# Easyhub.net
KiCad netlist of a schematic drawn in EasyEDA Pro
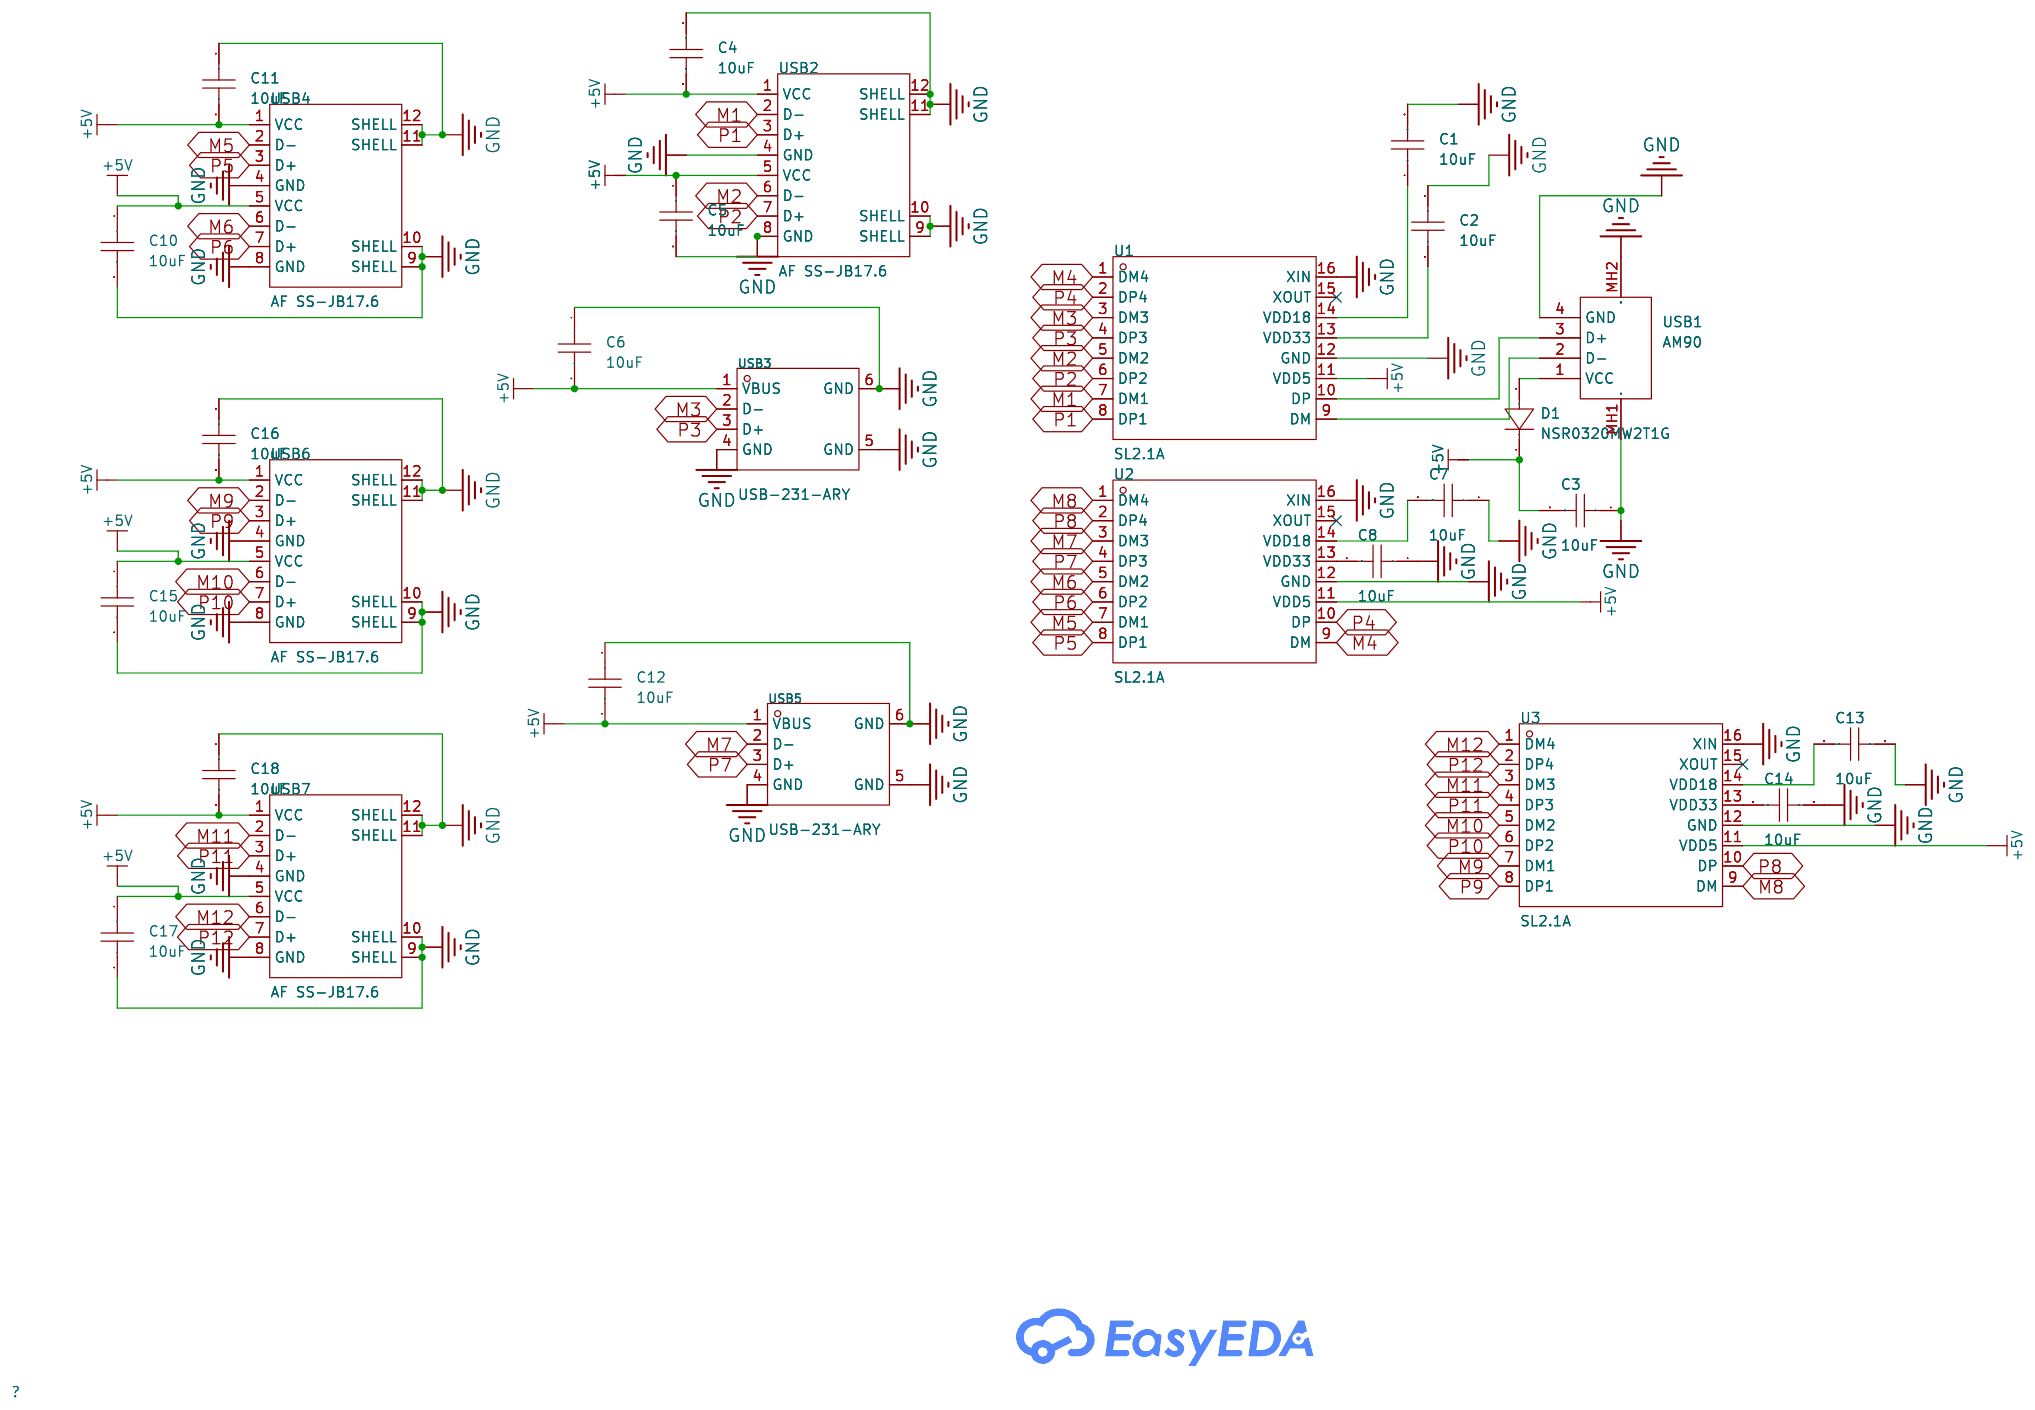
[diagram p0: schematic sheet]

(export (version "E")
  (design (tool "Eeschema 10.0.6"))
  (components
    (comp (ref "C1")
      (value "10uF")
      (footprint "easyedapro:C0603")
      (description "Capacitance:10uF Tolerance:±10% Tolerance:±10% Voltage Rating:10V Temperature Coefficient:X5R")
      (fields
        (field (name "Manufacturer Part") "CL10A106KP8NNNC")
        (field (name "Manufacturer") "SAMSUNG(三星)")
      )
      (libsource (lib "easyedapro") (part "CAP"))
    )
    (comp (ref "C2")
      (value "10uF")
      (footprint "easyedapro:C0603")
      (description "Capacitance:10uF Tolerance:±10% Tolerance:±10% Voltage Rating:10V Temperature Coefficient:X5R")
      (fields
        (field (name "Manufacturer Part") "CL10A106KP8NNNC")
        (field (name "Manufacturer") "SAMSUNG(三星)")
      )
      (libsource (lib "easyedapro") (part "CAP"))
    )
    (comp (ref "C3")
      (value "10uF")
      (footprint "easyedapro:C0603")
      (description "Capacitance:10uF Tolerance:±10% Tolerance:±10% Voltage Rating:10V Temperature Coefficient:X5R")
      (fields
        (field (name "Manufacturer Part") "CL10A106KP8NNNC")
        (field (name "Manufacturer") "SAMSUNG(三星)")
      )
      (libsource (lib "easyedapro") (part "CAP"))
    )
    (comp (ref "C4")
      (value "10uF")
      (footprint "easyedapro:C0603")
      (description "Capacitance:10uF Tolerance:±10% Tolerance:±10% Voltage Rating:10V Temperature Coefficient:X5R")
      (fields
        (field (name "Manufacturer Part") "CL10A106KP8NNNC")
        (field (name "Manufacturer") "SAMSUNG(三星)")
      )
      (libsource (lib "easyedapro") (part "CAP"))
    )
    (comp (ref "C5")
      (value "10uF")
      (footprint "easyedapro:C0603")
      (description "Capacitance:10uF Tolerance:±10% Tolerance:±10% Voltage Rating:10V Temperature Coefficient:X5R")
      (fields
        (field (name "Manufacturer Part") "CL10A106KP8NNNC")
        (field (name "Manufacturer") "SAMSUNG(三星)")
      )
      (libsource (lib "easyedapro") (part "CAP"))
    )
    (comp (ref "C6")
      (value "10uF")
      (footprint "easyedapro:C0603")
      (description "Capacitance:10uF Tolerance:±10% Tolerance:±10% Voltage Rating:10V Temperature Coefficient:X5R")
      (fields
        (field (name "Manufacturer Part") "CL10A106KP8NNNC")
        (field (name "Manufacturer") "SAMSUNG(三星)")
      )
      (libsource (lib "easyedapro") (part "CAP"))
    )
    (comp (ref "C7")
      (value "10uF")
      (footprint "easyedapro:C0603")
      (description "Capacitance:10uF Tolerance:±10% Tolerance:±10% Voltage Rating:10V Temperature Coefficient:X5R")
      (fields
        (field (name "Manufacturer Part") "CL10A106KP8NNNC")
        (field (name "Manufacturer") "SAMSUNG(三星)")
      )
      (libsource (lib "easyedapro") (part "CAP"))
    )
    (comp (ref "C8")
      (value "10uF")
      (footprint "easyedapro:C0603")
      (description "Capacitance:10uF Tolerance:±10% Tolerance:±10% Voltage Rating:10V Temperature Coefficient:X5R")
      (fields
        (field (name "Manufacturer Part") "CL10A106KP8NNNC")
        (field (name "Manufacturer") "SAMSUNG(三星)")
      )
      (libsource (lib "easyedapro") (part "CAP"))
    )
    (comp (ref "C10")
      (value "10uF")
      (footprint "easyedapro:C0603")
      (description "Capacitance:10uF Tolerance:±10% Tolerance:±10% Voltage Rating:10V Temperature Coefficient:X5R")
      (fields
        (field (name "Manufacturer Part") "CL10A106KP8NNNC")
        (field (name "Manufacturer") "SAMSUNG(三星)")
      )
      (libsource (lib "easyedapro") (part "CAP"))
    )
    (comp (ref "C11")
      (value "10uF")
      (footprint "easyedapro:C0603")
      (description "Capacitance:10uF Tolerance:±10% Tolerance:±10% Voltage Rating:10V Temperature Coefficient:X5R")
      (fields
        (field (name "Manufacturer Part") "CL10A106KP8NNNC")
        (field (name "Manufacturer") "SAMSUNG(三星)")
      )
      (libsource (lib "easyedapro") (part "CAP"))
    )
    (comp (ref "C12")
      (value "10uF")
      (footprint "easyedapro:C0603")
      (description "Capacitance:10uF Tolerance:±10% Tolerance:±10% Voltage Rating:10V Temperature Coefficient:X5R")
      (fields
        (field (name "Manufacturer Part") "CL10A106KP8NNNC")
        (field (name "Manufacturer") "SAMSUNG(三星)")
      )
      (libsource (lib "easyedapro") (part "CAP"))
    )
    (comp (ref "C13")
      (value "10uF")
      (footprint "easyedapro:C0603")
      (description "Capacitance:10uF Tolerance:±10% Tolerance:±10% Voltage Rating:10V Temperature Coefficient:X5R")
      (fields
        (field (name "Manufacturer Part") "CL10A106KP8NNNC")
        (field (name "Manufacturer") "SAMSUNG(三星)")
      )
      (libsource (lib "easyedapro") (part "CAP"))
    )
    (comp (ref "C14")
      (value "10uF")
      (footprint "easyedapro:C0603")
      (description "Capacitance:10uF Tolerance:±10% Tolerance:±10% Voltage Rating:10V Temperature Coefficient:X5R")
      (fields
        (field (name "Manufacturer Part") "CL10A106KP8NNNC")
        (field (name "Manufacturer") "SAMSUNG(三星)")
      )
      (libsource (lib "easyedapro") (part "CAP"))
    )
    (comp (ref "C15")
      (value "10uF")
      (footprint "easyedapro:C0603")
      (description "Capacitance:10uF Tolerance:±10% Tolerance:±10% Voltage Rating:10V Temperature Coefficient:X5R")
      (fields
        (field (name "Manufacturer Part") "CL10A106KP8NNNC")
        (field (name "Manufacturer") "SAMSUNG(三星)")
      )
      (libsource (lib "easyedapro") (part "CAP"))
    )
    (comp (ref "C16")
      (value "10uF")
      (footprint "easyedapro:C0603")
      (description "Capacitance:10uF Tolerance:±10% Tolerance:±10% Voltage Rating:10V Temperature Coefficient:X5R")
      (fields
        (field (name "Manufacturer Part") "CL10A106KP8NNNC")
        (field (name "Manufacturer") "SAMSUNG(三星)")
      )
      (libsource (lib "easyedapro") (part "CAP"))
    )
    (comp (ref "C17")
      (value "10uF")
      (footprint "easyedapro:C0603")
      (description "Capacitance:10uF Tolerance:±10% Tolerance:±10% Voltage Rating:10V Temperature Coefficient:X5R")
      (fields
        (field (name "Manufacturer Part") "CL10A106KP8NNNC")
        (field (name "Manufacturer") "SAMSUNG(三星)")
      )
      (libsource (lib "easyedapro") (part "CAP"))
    )
    (comp (ref "C18")
      (value "10uF")
      (footprint "easyedapro:C0603")
      (description "Capacitance:10uF Tolerance:±10% Tolerance:±10% Voltage Rating:10V Temperature Coefficient:X5R")
      (fields
        (field (name "Manufacturer Part") "CL10A106KP8NNNC")
        (field (name "Manufacturer") "SAMSUNG(三星)")
      )
      (libsource (lib "easyedapro") (part "CAP"))
    )
    (comp (ref "D1")
      (value "NSR0320MW2T1G")
      (footprint "easyedapro:SMA_L4.4-W2.8-LS5.4-RD")
      (fields (field (name "Manufacturer") "onsemi(安森美)"))
      (libsource (lib "easyedapro") (part "D_1N4007"))
    )
    (comp (ref "U1")
      (value "SL2.1A")
      (footprint "easyedapro:SOP-16_L10.0-W3.9-P1.27-LS6.0-BL")
      (fields (field (name "Manufacturer") "CoreChips(和芯润德)"))
      (libsource (lib "easyedapro") (part "SL2.1A_C6798314"))
    )
    (comp (ref "U2")
      (value "SL2.1A")
      (footprint "easyedapro:SOP-16_L10.0-W3.9-P1.27-LS6.0-BL")
      (fields (field (name "Manufacturer") "CoreChips(和芯润德)"))
      (libsource (lib "easyedapro") (part "SL2.1A_C6798314"))
    )
    (comp (ref "U3")
      (value "SL2.1A")
      (footprint "easyedapro:SOP-16_L10.0-W3.9-P1.27-LS6.0-BL")
      (fields (field (name "Manufacturer") "CoreChips(和芯润德)"))
      (libsource (lib "easyedapro") (part "SL2.1A_C6798314"))
    )
    (comp (ref "USB1")
      (value "AM90")
      (footprint "easyedapro:USB-AM-TH_AM90")
      (fields (field (name "Manufacturer") "SHOU HAN(首韩)"))
      (libsource (lib "easyedapro") (part "AM90"))
    )
    (comp (ref "USB2")
      (value "AF SS-JB17.6")
      (footprint "easyedapro:USB-A-TH_AF-SS-JB17.6")
      (fields (field (name "Manufacturer") "SHOU HAN(首韩)"))
      (libsource (lib "easyedapro") (part "AF SS-JB17.6"))
    )
    (comp (ref "USB3")
      (value "USB-231-ARY")
      (footprint "easyedapro:USB-A-TH_USB-231-ARY")
      (fields (field (name "Manufacturer") "XUNPU(讯普)"))
      (libsource (lib "easyedapro") (part "USB-231-ARY"))
    )
    (comp (ref "USB4")
      (value "AF SS-JB17.6")
      (footprint "easyedapro:USB-A-TH_AF-SS-JB17.6")
      (fields (field (name "Manufacturer") "SHOU HAN(首韩)"))
      (libsource (lib "easyedapro") (part "AF SS-JB17.6"))
    )
    (comp (ref "USB5")
      (value "USB-231-ARY")
      (footprint "easyedapro:USB-A-TH_USB-231-ARY")
      (fields (field (name "Manufacturer") "XUNPU(讯普)"))
      (libsource (lib "easyedapro") (part "USB-231-ARY"))
    )
    (comp (ref "USB6")
      (value "AF SS-JB17.6")
      (footprint "easyedapro:USB-A-TH_AF-SS-JB17.6")
      (fields (field (name "Manufacturer") "SHOU HAN(首韩)"))
      (libsource (lib "easyedapro") (part "AF SS-JB17.6"))
    )
    (comp (ref "USB7")
      (value "AF SS-JB17.6")
      (footprint "easyedapro:USB-A-TH_AF-SS-JB17.6")
      (fields (field (name "Manufacturer") "SHOU HAN(首韩)"))
      (libsource (lib "easyedapro") (part "AF SS-JB17.6"))
    )
  )
  (nets
    (net (code "1") (name "+5V") (class "Default")
      (node (ref "C10") (pin "1") (pinfunction "1_1") (pintype "input"))
      (node (ref "C11") (pin "2") (pinfunction "2_2") (pintype "input"))
      (node (ref "C12") (pin "2") (pinfunction "2_2") (pintype "input"))
      (node (ref "C15") (pin "1") (pinfunction "1_1") (pintype "input"))
      (node (ref "C16") (pin "2") (pinfunction "2_2") (pintype "input"))
      (node (ref "C17") (pin "1") (pinfunction "1_1") (pintype "input"))
      (node (ref "C18") (pin "2") (pinfunction "2_2") (pintype "input"))
      (node (ref "C3") (pin "2") (pinfunction "2_2") (pintype "input"))
      (node (ref "C4") (pin "2") (pinfunction "2_2") (pintype "input"))
      (node (ref "C5") (pin "1") (pinfunction "1_1") (pintype "input"))
      (node (ref "C6") (pin "2") (pinfunction "2_2") (pintype "input"))
      (node (ref "D1") (pin "1") (pinfunction "K_1") (pintype "input"))
      (node (ref "U1") (pin "11") (pinfunction "VDD5_11") (pintype "unspecified"))
      (node (ref "U2") (pin "11") (pinfunction "VDD5_11") (pintype "unspecified"))
      (node (ref "U3") (pin "11") (pinfunction "VDD5_11") (pintype "unspecified"))
      (node (ref "USB2") (pin "1") (pinfunction "VCC_1") (pintype "unspecified"))
      (node (ref "USB2") (pin "5") (pinfunction "VCC_5") (pintype "unspecified"))
      (node (ref "USB3") (pin "1") (pinfunction "VBUS_1") (pintype "input"))
      (node (ref "USB4") (pin "1") (pinfunction "VCC_1") (pintype "unspecified"))
      (node (ref "USB4") (pin "5") (pinfunction "VCC_5") (pintype "unspecified"))
      (node (ref "USB5") (pin "1") (pinfunction "VBUS_1") (pintype "input"))
      (node (ref "USB6") (pin "1") (pinfunction "VCC_1") (pintype "unspecified"))
      (node (ref "USB6") (pin "5") (pinfunction "VCC_5") (pintype "unspecified"))
      (node (ref "USB7") (pin "1") (pinfunction "VCC_1") (pintype "unspecified"))
      (node (ref "USB7") (pin "5") (pinfunction "VCC_5") (pintype "unspecified"))
    )
    (net (code "2") (name "GND") (class "Default")
      (node (ref "C1") (pin "2") (pinfunction "2_2") (pintype "input"))
      (node (ref "C10") (pin "2") (pinfunction "2_2") (pintype "input"))
      (node (ref "C11") (pin "1") (pinfunction "1_1") (pintype "input"))
      (node (ref "C12") (pin "1") (pinfunction "1_1") (pintype "input"))
      (node (ref "C13") (pin "1") (pinfunction "1_1") (pintype "input"))
      (node (ref "C14") (pin "1") (pinfunction "1_1") (pintype "input"))
      (node (ref "C15") (pin "2") (pinfunction "2_2") (pintype "input"))
      (node (ref "C16") (pin "1") (pinfunction "1_1") (pintype "input"))
      (node (ref "C17") (pin "2") (pinfunction "2_2") (pintype "input"))
      (node (ref "C18") (pin "1") (pinfunction "1_1") (pintype "input"))
      (node (ref "C2") (pin "1") (pinfunction "1_1") (pintype "input"))
      (node (ref "C3") (pin "1") (pinfunction "1_1") (pintype "input"))
      (node (ref "C4") (pin "1") (pinfunction "1_1") (pintype "input"))
      (node (ref "C5") (pin "2") (pinfunction "2_2") (pintype "input"))
      (node (ref "C6") (pin "1") (pinfunction "1_1") (pintype "input"))
      (node (ref "C7") (pin "1") (pinfunction "1_1") (pintype "input"))
      (node (ref "C8") (pin "1") (pinfunction "1_1") (pintype "input"))
      (node (ref "U1") (pin "12") (pinfunction "GND_12") (pintype "unspecified"))
      (node (ref "U1") (pin "16") (pinfunction "XIN_16") (pintype "unspecified"))
      (node (ref "U2") (pin "12") (pinfunction "GND_12") (pintype "unspecified"))
      (node (ref "U2") (pin "16") (pinfunction "XIN_16") (pintype "unspecified"))
      (node (ref "U3") (pin "12") (pinfunction "GND_12") (pintype "unspecified"))
      (node (ref "U3") (pin "16") (pinfunction "XIN_16") (pintype "unspecified"))
      (node (ref "USB1") (pin "4") (pinfunction "GND_4") (pintype "input"))
      (node (ref "USB1") (pin "MH1") (pinfunction "MH1_MH1") (pintype "unspecified"))
      (node (ref "USB1") (pin "MH2") (pinfunction "MH2_MH2") (pintype "unspecified"))
      (node (ref "USB2") (pin "10") (pinfunction "SHELL_10") (pintype "unspecified"))
      (node (ref "USB2") (pin "11") (pinfunction "SHELL_11") (pintype "unspecified"))
      (node (ref "USB2") (pin "12") (pinfunction "SHELL_12") (pintype "unspecified"))
      (node (ref "USB2") (pin "4") (pinfunction "GND_4") (pintype "unspecified"))
      (node (ref "USB2") (pin "8") (pinfunction "GND_8") (pintype "unspecified"))
      (node (ref "USB2") (pin "9") (pinfunction "SHELL_9") (pintype "unspecified"))
      (node (ref "USB3") (pin "4") (pinfunction "GND_4") (pintype "input"))
      (node (ref "USB3") (pin "5") (pinfunction "GND_5") (pintype "input"))
      (node (ref "USB3") (pin "6") (pinfunction "GND_6") (pintype "input"))
      (node (ref "USB4") (pin "10") (pinfunction "SHELL_10") (pintype "unspecified"))
      (node (ref "USB4") (pin "11") (pinfunction "SHELL_11") (pintype "unspecified"))
      (node (ref "USB4") (pin "12") (pinfunction "SHELL_12") (pintype "unspecified"))
      (node (ref "USB4") (pin "4") (pinfunction "GND_4") (pintype "unspecified"))
      (node (ref "USB4") (pin "8") (pinfunction "GND_8") (pintype "unspecified"))
      (node (ref "USB4") (pin "9") (pinfunction "SHELL_9") (pintype "unspecified"))
      (node (ref "USB5") (pin "4") (pinfunction "GND_4") (pintype "input"))
      (node (ref "USB5") (pin "5") (pinfunction "GND_5") (pintype "input"))
      (node (ref "USB5") (pin "6") (pinfunction "GND_6") (pintype "input"))
      (node (ref "USB6") (pin "10") (pinfunction "SHELL_10") (pintype "unspecified"))
      (node (ref "USB6") (pin "11") (pinfunction "SHELL_11") (pintype "unspecified"))
      (node (ref "USB6") (pin "12") (pinfunction "SHELL_12") (pintype "unspecified"))
      (node (ref "USB6") (pin "4") (pinfunction "GND_4") (pintype "unspecified"))
      (node (ref "USB6") (pin "8") (pinfunction "GND_8") (pintype "unspecified"))
      (node (ref "USB6") (pin "9") (pinfunction "SHELL_9") (pintype "unspecified"))
      (node (ref "USB7") (pin "10") (pinfunction "SHELL_10") (pintype "unspecified"))
      (node (ref "USB7") (pin "11") (pinfunction "SHELL_11") (pintype "unspecified"))
      (node (ref "USB7") (pin "12") (pinfunction "SHELL_12") (pintype "unspecified"))
      (node (ref "USB7") (pin "4") (pinfunction "GND_4") (pintype "unspecified"))
      (node (ref "USB7") (pin "8") (pinfunction "GND_8") (pintype "unspecified"))
      (node (ref "USB7") (pin "9") (pinfunction "SHELL_9") (pintype "unspecified"))
    )
    (net (code "3") (name "M1") (class "Default")
      (node (ref "U1") (pin "7") (pinfunction "DM1_7") (pintype "unspecified"))
      (node (ref "USB2") (pin "2") (pinfunction "D-_2") (pintype "unspecified"))
    )
    (net (code "4") (name "M2") (class "Default")
      (node (ref "U1") (pin "5") (pinfunction "DM2_5") (pintype "unspecified"))
      (node (ref "USB2") (pin "6") (pinfunction "D-_6") (pintype "unspecified"))
    )
    (net (code "5") (name "M3") (class "Default")
      (node (ref "U1") (pin "3") (pinfunction "DM3_3") (pintype "unspecified"))
      (node (ref "USB3") (pin "2") (pinfunction "D-_2") (pintype "input"))
    )
    (net (code "6") (name "M4") (class "Default")
      (node (ref "U1") (pin "1") (pinfunction "DM4_1") (pintype "unspecified"))
      (node (ref "U2") (pin "9") (pinfunction "DM_9") (pintype "unspecified"))
    )
    (net (code "7") (name "M5") (class "Default")
      (node (ref "U2") (pin "7") (pinfunction "DM1_7") (pintype "unspecified"))
      (node (ref "USB4") (pin "2") (pinfunction "D-_2") (pintype "unspecified"))
    )
    (net (code "8") (name "M6") (class "Default")
      (node (ref "U2") (pin "5") (pinfunction "DM2_5") (pintype "unspecified"))
      (node (ref "USB4") (pin "6") (pinfunction "D-_6") (pintype "unspecified"))
    )
    (net (code "9") (name "M7") (class "Default")
      (node (ref "U2") (pin "3") (pinfunction "DM3_3") (pintype "unspecified"))
      (node (ref "USB5") (pin "2") (pinfunction "D-_2") (pintype "input"))
    )
    (net (code "10") (name "M8") (class "Default")
      (node (ref "U2") (pin "1") (pinfunction "DM4_1") (pintype "unspecified"))
      (node (ref "U3") (pin "9") (pinfunction "DM_9") (pintype "unspecified"))
    )
    (net (code "11") (name "M9") (class "Default")
      (node (ref "U3") (pin "7") (pinfunction "DM1_7") (pintype "unspecified"))
      (node (ref "USB6") (pin "2") (pinfunction "D-_2") (pintype "unspecified"))
    )
    (net (code "12") (name "M10") (class "Default")
      (node (ref "U3") (pin "5") (pinfunction "DM2_5") (pintype "unspecified"))
      (node (ref "USB6") (pin "6") (pinfunction "D-_6") (pintype "unspecified"))
    )
    (net (code "13") (name "M11") (class "Default")
      (node (ref "U3") (pin "3") (pinfunction "DM3_3") (pintype "unspecified"))
      (node (ref "USB7") (pin "2") (pinfunction "D-_2") (pintype "unspecified"))
    )
    (net (code "14") (name "M12") (class "Default")
      (node (ref "U3") (pin "1") (pinfunction "DM4_1") (pintype "unspecified"))
      (node (ref "USB7") (pin "6") (pinfunction "D-_6") (pintype "unspecified"))
    )
    (net (code "15") (name "Net-(D1-A)") (class "Default")
      (node (ref "D1") (pin "2") (pinfunction "A_2") (pintype "input"))
      (node (ref "USB1") (pin "1") (pinfunction "VCC_1") (pintype "input"))
    )
    (net (code "16") (name "Net-(U1-DM)") (class "Default")
      (node (ref "U1") (pin "9") (pinfunction "DM_9") (pintype "unspecified"))
      (node (ref "USB1") (pin "2") (pinfunction "D-_2") (pintype "input"))
    )
    (net (code "17") (name "Net-(U1-DP)") (class "Default")
      (node (ref "U1") (pin "10") (pinfunction "DP_10") (pintype "unspecified"))
      (node (ref "USB1") (pin "3") (pinfunction "D+_3") (pintype "input"))
    )
    (net (code "18") (name "Net-(U1-VDD18)") (class "Default")
      (node (ref "C1") (pin "1") (pinfunction "1_1") (pintype "input"))
      (node (ref "U1") (pin "14") (pinfunction "VDD18_14") (pintype "unspecified"))
    )
    (net (code "19") (name "Net-(U1-VDD33)") (class "Default")
      (node (ref "C2") (pin "2") (pinfunction "2_2") (pintype "input"))
      (node (ref "U1") (pin "13") (pinfunction "VDD33_13") (pintype "unspecified"))
    )
    (net (code "20") (name "Net-(U2-VDD18)") (class "Default")
      (node (ref "C7") (pin "2") (pinfunction "2_2") (pintype "input"))
      (node (ref "U2") (pin "14") (pinfunction "VDD18_14") (pintype "unspecified"))
    )
    (net (code "21") (name "Net-(U2-VDD33)") (class "Default")
      (node (ref "C8") (pin "2") (pinfunction "2_2") (pintype "input"))
      (node (ref "U2") (pin "13") (pinfunction "VDD33_13") (pintype "unspecified"))
    )
    (net (code "22") (name "Net-(U3-VDD18)") (class "Default")
      (node (ref "C13") (pin "2") (pinfunction "2_2") (pintype "input"))
      (node (ref "U3") (pin "14") (pinfunction "VDD18_14") (pintype "unspecified"))
    )
    (net (code "23") (name "Net-(U3-VDD33)") (class "Default")
      (node (ref "C14") (pin "2") (pinfunction "2_2") (pintype "input"))
      (node (ref "U3") (pin "13") (pinfunction "VDD33_13") (pintype "unspecified"))
    )
    (net (code "24") (name "P1") (class "Default")
      (node (ref "U1") (pin "8") (pinfunction "DP1_8") (pintype "unspecified"))
      (node (ref "USB2") (pin "3") (pinfunction "D+_3") (pintype "unspecified"))
    )
    (net (code "25") (name "P2") (class "Default")
      (node (ref "U1") (pin "6") (pinfunction "DP2_6") (pintype "unspecified"))
      (node (ref "USB2") (pin "7") (pinfunction "D+_7") (pintype "unspecified"))
    )
    (net (code "26") (name "P3") (class "Default")
      (node (ref "U1") (pin "4") (pinfunction "DP3_4") (pintype "unspecified"))
      (node (ref "USB3") (pin "3") (pinfunction "D+_3") (pintype "input"))
    )
    (net (code "27") (name "P4") (class "Default")
      (node (ref "U1") (pin "2") (pinfunction "DP4_2") (pintype "unspecified"))
      (node (ref "U2") (pin "10") (pinfunction "DP_10") (pintype "unspecified"))
    )
    (net (code "28") (name "P5") (class "Default")
      (node (ref "U2") (pin "8") (pinfunction "DP1_8") (pintype "unspecified"))
      (node (ref "USB4") (pin "3") (pinfunction "D+_3") (pintype "unspecified"))
    )
    (net (code "29") (name "P6") (class "Default")
      (node (ref "U2") (pin "6") (pinfunction "DP2_6") (pintype "unspecified"))
      (node (ref "USB4") (pin "7") (pinfunction "D+_7") (pintype "unspecified"))
    )
    (net (code "30") (name "P7") (class "Default")
      (node (ref "U2") (pin "4") (pinfunction "DP3_4") (pintype "unspecified"))
      (node (ref "USB5") (pin "3") (pinfunction "D+_3") (pintype "input"))
    )
    (net (code "31") (name "P8") (class "Default")
      (node (ref "U2") (pin "2") (pinfunction "DP4_2") (pintype "unspecified"))
      (node (ref "U3") (pin "10") (pinfunction "DP_10") (pintype "unspecified"))
    )
    (net (code "32") (name "P9") (class "Default")
      (node (ref "U3") (pin "8") (pinfunction "DP1_8") (pintype "unspecified"))
      (node (ref "USB6") (pin "3") (pinfunction "D+_3") (pintype "unspecified"))
    )
    (net (code "33") (name "P10") (class "Default")
      (node (ref "U3") (pin "6") (pinfunction "DP2_6") (pintype "unspecified"))
      (node (ref "USB6") (pin "7") (pinfunction "D+_7") (pintype "unspecified"))
    )
    (net (code "34") (name "P11") (class "Default")
      (node (ref "U3") (pin "4") (pinfunction "DP3_4") (pintype "unspecified"))
      (node (ref "USB7") (pin "3") (pinfunction "D+_3") (pintype "unspecified"))
    )
    (net (code "35") (name "P12") (class "Default")
      (node (ref "U3") (pin "2") (pinfunction "DP4_2") (pintype "unspecified"))
      (node (ref "USB7") (pin "7") (pinfunction "D+_7") (pintype "unspecified"))
    )
    (net (code "36") (name "unconnected-(U1-XOUT-Pad15)") (class "Default")
      (node (ref "U1") (pin "15") (pinfunction "XOUT_15") (pintype "unspecified+no_connect"))
    )
    (net (code "37") (name "unconnected-(U2-XOUT-Pad15)") (class "Default")
      (node (ref "U2") (pin "15") (pinfunction "XOUT_15") (pintype "unspecified+no_connect"))
    )
    (net (code "38") (name "unconnected-(U3-XOUT-Pad15)") (class "Default")
      (node (ref "U3") (pin "15") (pinfunction "XOUT_15") (pintype "unspecified+no_connect"))
    )
  )
)
